# Environment-ArduinoNano33-V10_1-Top.net
KiCad netlist of a schematic drawn in EAGLE
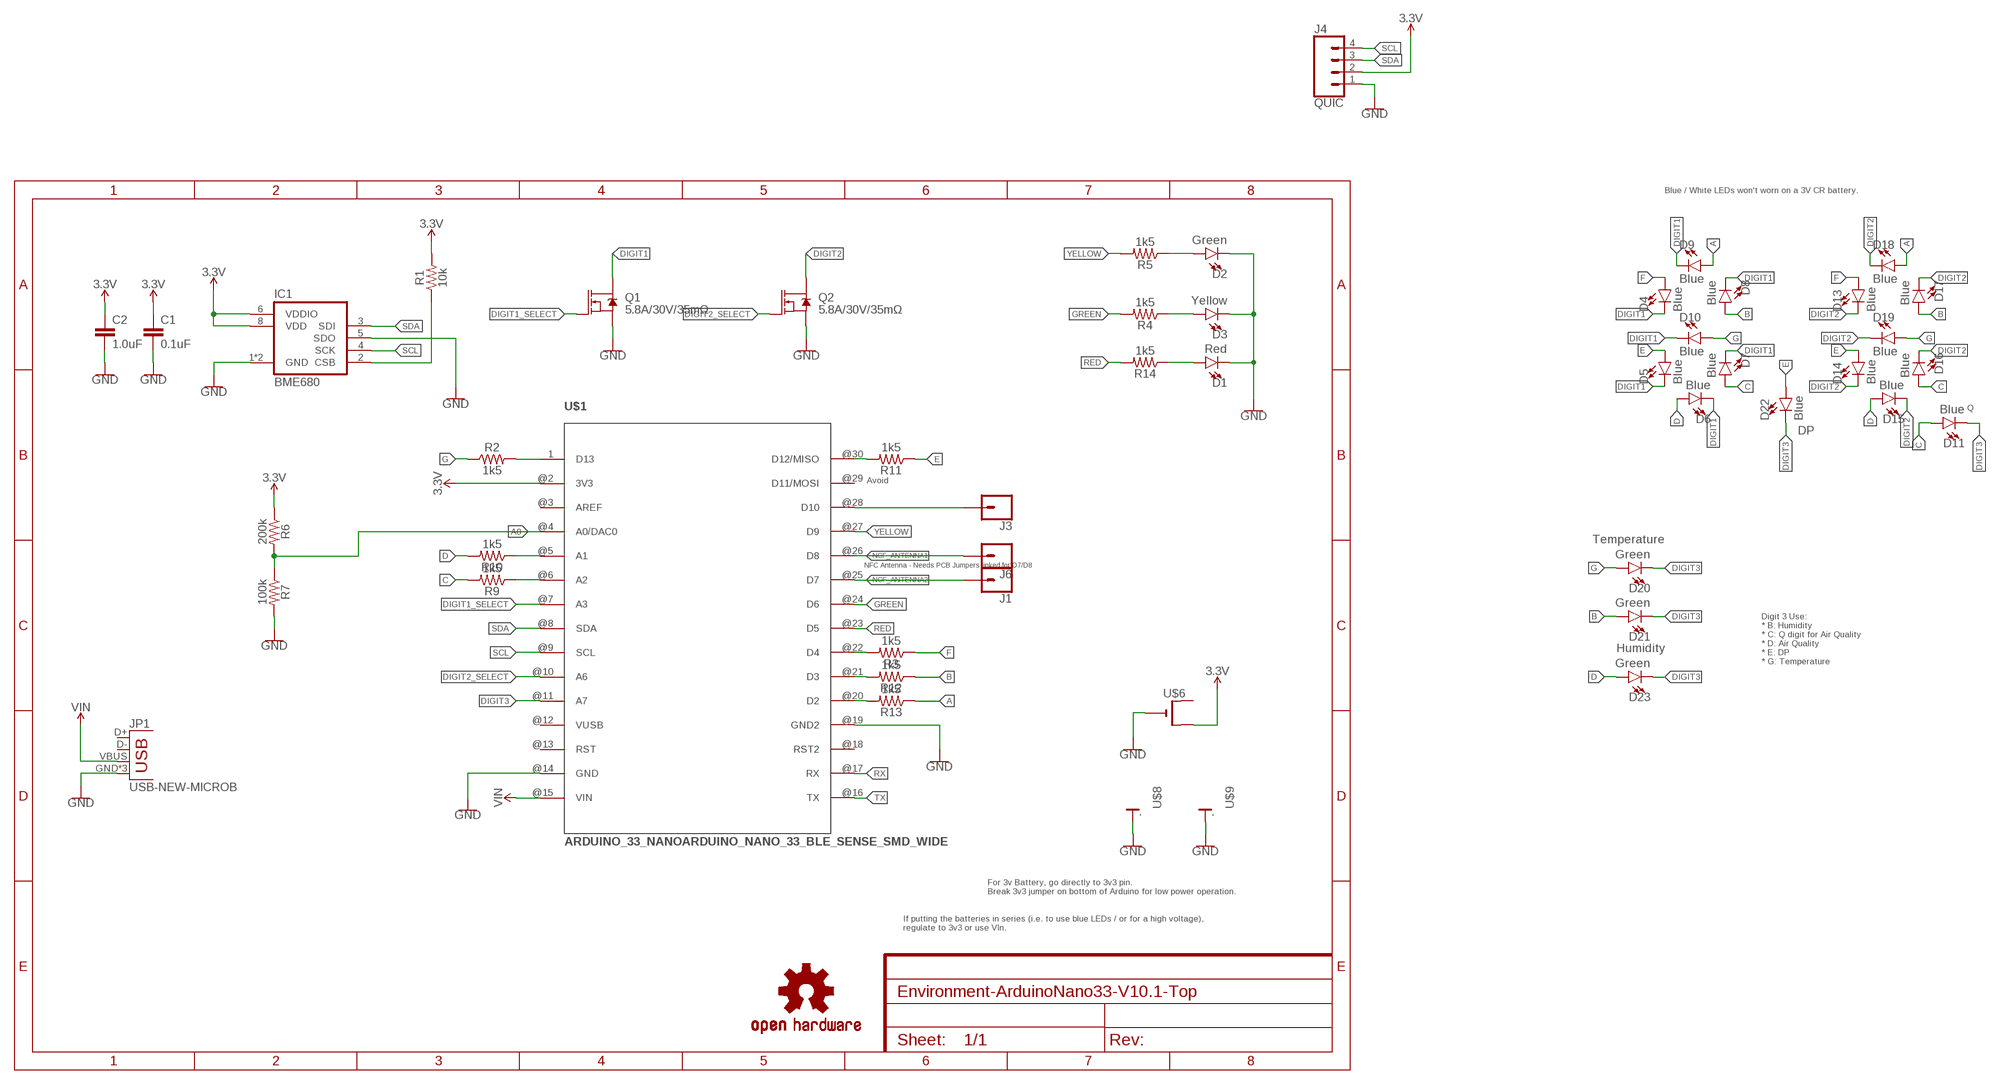
[diagram p0: schematic, sheet 1]

(export (version "E")
  (design (tool "Eeschema 10.0.6"))
  (components
    (comp (ref "C1")
      (value "0.1uF")
      (footprint "eagle-import:0805")
      (libsource (lib "eagle-import") (part "0.1UF-0805-25V"))
    )
    (comp (ref "C2")
      (value "1.0uF")
      (footprint "eagle-import:0805")
      (libsource (lib "eagle-import") (part "1.0UF-0805-25V-10%"))
    )
    (comp (ref "D1")
      (value "Red")
      (footprint "eagle-import:LED-1206")
      (libsource (lib "eagle-import") (part "LED1206"))
    )
    (comp (ref "D2")
      (value "Green")
      (footprint "eagle-import:LED-1206")
      (libsource (lib "eagle-import") (part "LED1206"))
    )
    (comp (ref "D3")
      (value "Yellow")
      (footprint "eagle-import:LED-1206")
      (libsource (lib "eagle-import") (part "LED1206"))
    )
    (comp (ref "D4")
      (value "Blue")
      (footprint "eagle-import:LED-1206")
      (libsource (lib "eagle-import") (part "LED1206"))
    )
    (comp (ref "D5")
      (value "Blue")
      (footprint "eagle-import:LED-1206")
      (libsource (lib "eagle-import") (part "LED1206"))
    )
    (comp (ref "D6")
      (value "Blue")
      (footprint "eagle-import:LED-1206")
      (libsource (lib "eagle-import") (part "LED1206"))
    )
    (comp (ref "D7")
      (value "Blue")
      (footprint "eagle-import:LED-1206")
      (libsource (lib "eagle-import") (part "LED1206"))
    )
    (comp (ref "D8")
      (value "Blue")
      (footprint "eagle-import:LED-1206")
      (libsource (lib "eagle-import") (part "LED1206"))
    )
    (comp (ref "D9")
      (value "Blue")
      (footprint "eagle-import:LED-1206")
      (libsource (lib "eagle-import") (part "LED1206"))
    )
    (comp (ref "D10")
      (value "Blue")
      (footprint "eagle-import:LED-1206")
      (libsource (lib "eagle-import") (part "LED1206"))
    )
    (comp (ref "D11")
      (value "Blue")
      (footprint "eagle-import:LED-1206")
      (libsource (lib "eagle-import") (part "LED1206"))
    )
    (comp (ref "D13")
      (value "Blue")
      (footprint "eagle-import:LED-1206")
      (libsource (lib "eagle-import") (part "LED1206"))
    )
    (comp (ref "D14")
      (value "Blue")
      (footprint "eagle-import:LED-1206")
      (libsource (lib "eagle-import") (part "LED1206"))
    )
    (comp (ref "D15")
      (value "Blue")
      (footprint "eagle-import:LED-1206")
      (libsource (lib "eagle-import") (part "LED1206"))
    )
    (comp (ref "D16")
      (value "Blue")
      (footprint "eagle-import:LED-1206")
      (libsource (lib "eagle-import") (part "LED1206"))
    )
    (comp (ref "D17")
      (value "Blue")
      (footprint "eagle-import:LED-1206")
      (libsource (lib "eagle-import") (part "LED1206"))
    )
    (comp (ref "D18")
      (value "Blue")
      (footprint "eagle-import:LED-1206")
      (libsource (lib "eagle-import") (part "LED1206"))
    )
    (comp (ref "D19")
      (value "Blue")
      (footprint "eagle-import:LED-1206")
      (libsource (lib "eagle-import") (part "LED1206"))
    )
    (comp (ref "D20")
      (value "Green")
      (footprint "eagle-import:LED-1206")
      (libsource (lib "eagle-import") (part "LED1206"))
    )
    (comp (ref "D21")
      (value "Green")
      (footprint "eagle-import:LED-1206")
      (libsource (lib "eagle-import") (part "LED1206"))
    )
    (comp (ref "D22")
      (value "Blue")
      (footprint "eagle-import:LED-1206")
      (libsource (lib "eagle-import") (part "LED1206"))
    )
    (comp (ref "D23")
      (value "Green")
      (footprint "eagle-import:LED-1206")
      (libsource (lib "eagle-import") (part "LED1206"))
    )
    (comp (ref "IC1")
      (value "BME680")
      (footprint "eagle-import:BME680")
      (libsource (lib "eagle-import") (part "BME680"))
    )
    (comp (ref "J1")
      (value "CONN_01")
      (footprint "eagle-import:1X01")
      (libsource (lib "eagle-import") (part "CONN_01"))
    )
    (comp (ref "J3")
      (value "CONN_01")
      (footprint "eagle-import:1X01")
      (libsource (lib "eagle-import") (part "CONN_01"))
    )
    (comp (ref "J4")
      (value "QUIC")
      (footprint "eagle-import:JST04_1MM_RA")
      (libsource (lib "eagle-import") (part "CONN_04SMD2"))
    )
    (comp (ref "J6")
      (value "CONN_01")
      (footprint "eagle-import:1X01")
      (libsource (lib "eagle-import") (part "CONN_01"))
    )
    (comp (ref "JP1")
      (value "USB-NEW-MICROB")
      (footprint "eagle-import:USB-MICROB")
      (libsource (lib "eagle-import") (part "USB-NEW-MICROB"))
    )
    (comp (ref "LOGO1")
      (value "OSHW-LOGOM")
      (footprint "eagle-import:OSHW-LOGO-M")
      (libsource (lib "eagle-import") (part "OSHW-LOGOM"))
    )
    (comp (ref "Q1")
      (value "5.8A/30V/35mΩ")
      (footprint "eagle-import:SOT23-3")
      (libsource (lib "eagle-import") (part "MOSFET-NCH-AO3404A"))
    )
    (comp (ref "Q2")
      (value "5.8A/30V/35mΩ")
      (footprint "eagle-import:SOT23-3")
      (libsource (lib "eagle-import") (part "MOSFET-NCH-AO3404A"))
    )
    (comp (ref "R1")
      (value "10k")
      (footprint "eagle-import:0805")
      (libsource (lib "eagle-import") (part "RESISTOR0805"))
    )
    (comp (ref "R2")
      (value "1k5")
      (footprint "eagle-import:0805")
      (libsource (lib "eagle-import") (part "RESISTOR0805"))
    )
    (comp (ref "R3")
      (value "1k5")
      (footprint "eagle-import:0805")
      (libsource (lib "eagle-import") (part "RESISTOR0805"))
    )
    (comp (ref "R4")
      (value "1k5")
      (footprint "eagle-import:0805")
      (libsource (lib "eagle-import") (part "RESISTOR0805"))
    )
    (comp (ref "R5")
      (value "1k5")
      (footprint "eagle-import:0805")
      (libsource (lib "eagle-import") (part "RESISTOR0805"))
    )
    (comp (ref "R6")
      (value "200k")
      (footprint "eagle-import:0805")
      (libsource (lib "eagle-import") (part "RESISTOR0805"))
    )
    (comp (ref "R7")
      (value "100k")
      (footprint "eagle-import:0805")
      (libsource (lib "eagle-import") (part "RESISTOR0805"))
    )
    (comp (ref "R9")
      (value "1k5")
      (footprint "eagle-import:0805")
      (libsource (lib "eagle-import") (part "RESISTOR0805"))
    )
    (comp (ref "R10")
      (value "1k5")
      (footprint "eagle-import:0805")
      (libsource (lib "eagle-import") (part "RESISTOR0805"))
    )
    (comp (ref "R11")
      (value "1k5")
      (footprint "eagle-import:0805")
      (libsource (lib "eagle-import") (part "RESISTOR0805"))
    )
    (comp (ref "R12")
      (value "1k5")
      (footprint "eagle-import:0805")
      (libsource (lib "eagle-import") (part "RESISTOR0805"))
    )
    (comp (ref "R13")
      (value "1k5")
      (footprint "eagle-import:0805")
      (libsource (lib "eagle-import") (part "RESISTOR0805"))
    )
    (comp (ref "R14")
      (value "1k5")
      (footprint "eagle-import:0805")
      (libsource (lib "eagle-import") (part "RESISTOR0805"))
    )
    (comp (ref "U$1")
      (value "ARDUINO_33_NANOARDUINO_NANO_33_BLE_SENSE_SMD_WIDE")
      (footprint "eagle-import:ARDUINO_NANO_33_SMD_WIDER_PADS")
      (libsource (lib "eagle-import") (part "ARDUINO_33_NANOARDUINO_NANO_33_BLE_SENSE_SMD_WIDE"))
    )
    (comp (ref "U$6")
      (value "CR2032SMT")
      (footprint "eagle-import:CR2032-SMD")
      (libsource (lib "eagle-import") (part "CR2032SMT"))
    )
    (comp (ref "U$8")
      (value "CR2032-SPLIT-PCBCR2032-NEGATIVE")
      (footprint "eagle-import:CR2032-SMD-NEGATIVE-TERMINAL")
      (libsource (lib "eagle-import") (part "CR2032-SPLIT-PCBCR2032-NEGATIVE"))
    )
    (comp (ref "U$9")
      (value "CR2032-SPLIT-PCBCR2032-NEGATIVE")
      (footprint "eagle-import:CR2032-SMD-NEGATIVE-TERMINAL")
      (libsource (lib "eagle-import") (part "CR2032-SPLIT-PCBCR2032-NEGATIVE"))
    )
  )
  (nets
    (net (code "1") (name "/VUSB") (class "Default")
      (node (ref "U$1") (pin "@12") (pinfunction "VUSB_@12") (pintype "power_in"))
    )
    (net (code "2") (name "3.3V") (class "Default")
      (node (ref "C1") (pin "1") (pinfunction "1_1") (pintype "passive"))
      (node (ref "C2") (pin "1") (pinfunction "1_1") (pintype "passive"))
      (node (ref "IC1") (pin "6") (pinfunction "VDDIO_6") (pintype "power_in"))
      (node (ref "IC1") (pin "8") (pinfunction "VDD_8") (pintype "power_in"))
      (node (ref "J4") (pin "2") (pinfunction "2_2") (pintype "passive"))
      (node (ref "R1") (pin "2") (pinfunction "2_2") (pintype "passive"))
      (node (ref "R6") (pin "1") (pinfunction "1_1") (pintype "passive"))
      (node (ref "U$1") (pin "@2") (pinfunction "3V3_@2") (pintype "power_in"))
      (node (ref "U$6") (pin "+$2") (pinfunction "+1_+$2") (pintype "passive"))
    )
    (net (code "3") (name "A") (class "Default")
      (node (ref "D18") (pin "A") (pinfunction "A_A") (pintype "passive"))
      (node (ref "D9") (pin "A") (pinfunction "A_A") (pintype "passive"))
      (node (ref "R13") (pin "1") (pinfunction "1_1") (pintype "passive"))
    )
    (net (code "4") (name "A0") (class "Default")
      (node (ref "R6") (pin "2") (pinfunction "2_2") (pintype "passive"))
      (node (ref "R7") (pin "1") (pinfunction "1_1") (pintype "passive"))
      (node (ref "U$1") (pin "@4") (pinfunction "A0/DAC0_@4") (pintype "bidirectional"))
    )
    (net (code "5") (name "B") (class "Default")
      (node (ref "D17") (pin "A") (pinfunction "A_A") (pintype "passive"))
      (node (ref "D21") (pin "A") (pinfunction "A_A") (pintype "passive"))
      (node (ref "D8") (pin "A") (pinfunction "A_A") (pintype "passive"))
      (node (ref "R12") (pin "1") (pinfunction "1_1") (pintype "passive"))
    )
    (net (code "6") (name "C") (class "Default")
      (node (ref "D11") (pin "A") (pinfunction "A_A") (pintype "passive"))
      (node (ref "D16") (pin "A") (pinfunction "A_A") (pintype "passive"))
      (node (ref "D7") (pin "A") (pinfunction "A_A") (pintype "passive"))
      (node (ref "R9") (pin "2") (pinfunction "2_2") (pintype "passive"))
    )
    (net (code "7") (name "D") (class "Default")
      (node (ref "D15") (pin "A") (pinfunction "A_A") (pintype "passive"))
      (node (ref "D23") (pin "A") (pinfunction "A_A") (pintype "passive"))
      (node (ref "D6") (pin "A") (pinfunction "A_A") (pintype "passive"))
      (node (ref "R10") (pin "2") (pinfunction "2_2") (pintype "passive"))
    )
    (net (code "8") (name "DIGIT1") (class "Default")
      (node (ref "D10") (pin "C") (pinfunction "C_C") (pintype "passive"))
      (node (ref "D4") (pin "C") (pinfunction "C_C") (pintype "passive"))
      (node (ref "D5") (pin "C") (pinfunction "C_C") (pintype "passive"))
      (node (ref "D6") (pin "C") (pinfunction "C_C") (pintype "passive"))
      (node (ref "D7") (pin "C") (pinfunction "C_C") (pintype "passive"))
      (node (ref "D8") (pin "C") (pinfunction "C_C") (pintype "passive"))
      (node (ref "D9") (pin "C") (pinfunction "C_C") (pintype "passive"))
      (node (ref "Q1") (pin "3") (pinfunction "D_3") (pintype "bidirectional"))
    )
    (net (code "9") (name "DIGIT1_SELECT") (class "Default")
      (node (ref "Q1") (pin "1") (pinfunction "G_1") (pintype "bidirectional"))
      (node (ref "U$1") (pin "@7") (pinfunction "A3_@7") (pintype "bidirectional"))
    )
    (net (code "10") (name "DIGIT2") (class "Default")
      (node (ref "D13") (pin "C") (pinfunction "C_C") (pintype "passive"))
      (node (ref "D14") (pin "C") (pinfunction "C_C") (pintype "passive"))
      (node (ref "D15") (pin "C") (pinfunction "C_C") (pintype "passive"))
      (node (ref "D16") (pin "C") (pinfunction "C_C") (pintype "passive"))
      (node (ref "D17") (pin "C") (pinfunction "C_C") (pintype "passive"))
      (node (ref "D18") (pin "C") (pinfunction "C_C") (pintype "passive"))
      (node (ref "D19") (pin "C") (pinfunction "C_C") (pintype "passive"))
      (node (ref "Q2") (pin "3") (pinfunction "D_3") (pintype "bidirectional"))
    )
    (net (code "11") (name "DIGIT2_SELECT") (class "Default")
      (node (ref "Q2") (pin "1") (pinfunction "G_1") (pintype "bidirectional"))
      (node (ref "U$1") (pin "@10") (pinfunction "A6_@10") (pintype "bidirectional"))
    )
    (net (code "12") (name "DIGIT3") (class "Default")
      (node (ref "D11") (pin "C") (pinfunction "C_C") (pintype "passive"))
      (node (ref "D20") (pin "C") (pinfunction "C_C") (pintype "passive"))
      (node (ref "D21") (pin "C") (pinfunction "C_C") (pintype "passive"))
      (node (ref "D22") (pin "C") (pinfunction "C_C") (pintype "passive"))
      (node (ref "D23") (pin "C") (pinfunction "C_C") (pintype "passive"))
      (node (ref "U$1") (pin "@11") (pinfunction "A7_@11") (pintype "bidirectional"))
    )
    (net (code "13") (name "E") (class "Default")
      (node (ref "D14") (pin "A") (pinfunction "A_A") (pintype "passive"))
      (node (ref "D22") (pin "A") (pinfunction "A_A") (pintype "passive"))
      (node (ref "D5") (pin "A") (pinfunction "A_A") (pintype "passive"))
      (node (ref "R11") (pin "1") (pinfunction "1_1") (pintype "passive"))
    )
    (net (code "14") (name "F") (class "Default")
      (node (ref "D13") (pin "A") (pinfunction "A_A") (pintype "passive"))
      (node (ref "D4") (pin "A") (pinfunction "A_A") (pintype "passive"))
      (node (ref "R3") (pin "1") (pinfunction "1_1") (pintype "passive"))
    )
    (net (code "15") (name "G") (class "Default")
      (node (ref "D10") (pin "A") (pinfunction "A_A") (pintype "passive"))
      (node (ref "D19") (pin "A") (pinfunction "A_A") (pintype "passive"))
      (node (ref "D20") (pin "A") (pinfunction "A_A") (pintype "passive"))
      (node (ref "R2") (pin "1") (pinfunction "1_1") (pintype "passive"))
    )
    (net (code "16") (name "GND") (class "Default")
      (node (ref "C1") (pin "2") (pinfunction "2_2") (pintype "passive"))
      (node (ref "C2") (pin "2") (pinfunction "2_2") (pintype "passive"))
      (node (ref "D1") (pin "C") (pinfunction "C_C") (pintype "passive"))
      (node (ref "D2") (pin "C") (pinfunction "C_C") (pintype "passive"))
      (node (ref "D3") (pin "C") (pinfunction "C_C") (pintype "passive"))
      (node (ref "IC1") (pin "1") (pinfunction "GND_1") (pintype "power_in"))
      (node (ref "IC1") (pin "5") (pinfunction "SDO_5") (pintype "output"))
      (node (ref "IC1") (pin "7") (pinfunction "GND_7") (pintype "power_in"))
      (node (ref "J4") (pin "1") (pinfunction "1_1") (pintype "passive"))
      (node (ref "JP1") (pin "GND") (pinfunction "GND_GND") (pintype "bidirectional"))
      (node (ref "JP1") (pin "MT1") (pinfunction "GND_MT1") (pintype "bidirectional"))
      (node (ref "JP1") (pin "MT2") (pinfunction "GND_MT2") (pintype "bidirectional"))
      (node (ref "Q1") (pin "2") (pinfunction "S_2") (pintype "bidirectional"))
      (node (ref "Q2") (pin "2") (pinfunction "S_2") (pintype "bidirectional"))
      (node (ref "R7") (pin "2") (pinfunction "2_2") (pintype "passive"))
      (node (ref "U$1") (pin "@14") (pinfunction "GND_@14") (pintype "bidirectional"))
      (node (ref "U$1") (pin "@19") (pinfunction "GND2_@19") (pintype "bidirectional"))
      (node (ref "U$6") (pin "-") (pinfunction "-_-") (pintype "passive"))
      (node (ref "U$8") (pin "-") (pinfunction "-_-") (pintype "power_in"))
      (node (ref "U$9") (pin "-") (pinfunction "-_-") (pintype "power_in"))
    )
    (net (code "17") (name "GREEN") (class "Default")
      (node (ref "R4") (pin "2") (pinfunction "2_2") (pintype "passive"))
      (node (ref "U$1") (pin "@24") (pinfunction "D6_@24") (pintype "bidirectional"))
    )
    (net (code "18") (name "NCF_ANTENNA1") (class "Default")
      (node (ref "J6") (pin "1") (pinfunction "1_1") (pintype "passive"))
      (node (ref "U$1") (pin "@26") (pinfunction "D8_@26") (pintype "bidirectional"))
    )
    (net (code "19") (name "NCF_ANTENNA2") (class "Default")
      (node (ref "J1") (pin "1") (pinfunction "1_1") (pintype "passive"))
      (node (ref "U$1") (pin "@25") (pinfunction "D7_@25") (pintype "bidirectional"))
    )
    (net (code "20") (name "Net-(D1-PadA)") (class "Default")
      (node (ref "D1") (pin "A") (pinfunction "A_A") (pintype "passive"))
      (node (ref "R14") (pin "1") (pinfunction "1_1") (pintype "passive"))
    )
    (net (code "21") (name "Net-(D2-PadA)") (class "Default")
      (node (ref "D2") (pin "A") (pinfunction "A_A") (pintype "passive"))
      (node (ref "R5") (pin "1") (pinfunction "1_1") (pintype "passive"))
    )
    (net (code "22") (name "Net-(D3-PadA)") (class "Default")
      (node (ref "D3") (pin "A") (pinfunction "A_A") (pintype "passive"))
      (node (ref "R4") (pin "1") (pinfunction "1_1") (pintype "passive"))
    )
    (net (code "23") (name "Net-(IC1-CSB)") (class "Default")
      (node (ref "IC1") (pin "2") (pinfunction "CSB_2") (pintype "input"))
      (node (ref "R1") (pin "1") (pinfunction "1_1") (pintype "passive"))
    )
    (net (code "24") (name "Net-(U$1-A1)") (class "Default")
      (node (ref "R10") (pin "1") (pinfunction "1_1") (pintype "passive"))
      (node (ref "U$1") (pin "@5") (pinfunction "A1_@5") (pintype "bidirectional"))
    )
    (net (code "25") (name "Net-(U$1-A2)") (class "Default")
      (node (ref "R9") (pin "1") (pinfunction "1_1") (pintype "passive"))
      (node (ref "U$1") (pin "@6") (pinfunction "A2_@6") (pintype "bidirectional"))
    )
    (net (code "26") (name "Net-(U$1-D2)") (class "Default")
      (node (ref "R13") (pin "2") (pinfunction "2_2") (pintype "passive"))
      (node (ref "U$1") (pin "@20") (pinfunction "D2_@20") (pintype "bidirectional"))
    )
    (net (code "27") (name "Net-(U$1-D3)") (class "Default")
      (node (ref "R12") (pin "2") (pinfunction "2_2") (pintype "passive"))
      (node (ref "U$1") (pin "@21") (pinfunction "D3_@21") (pintype "bidirectional"))
    )
    (net (code "28") (name "Net-(U$1-D4)") (class "Default")
      (node (ref "R3") (pin "2") (pinfunction "2_2") (pintype "passive"))
      (node (ref "U$1") (pin "@22") (pinfunction "D4_@22") (pintype "bidirectional"))
    )
    (net (code "29") (name "Net-(U$1-D10)") (class "Default")
      (node (ref "J3") (pin "1") (pinfunction "1_1") (pintype "passive"))
      (node (ref "U$1") (pin "@28") (pinfunction "D10_@28") (pintype "bidirectional"))
    )
    (net (code "30") (name "Net-(U$1-D12{slash}MISO)") (class "Default")
      (node (ref "R11") (pin "2") (pinfunction "2_2") (pintype "passive"))
      (node (ref "U$1") (pin "@30") (pinfunction "D12/MISO_@30") (pintype "bidirectional"))
    )
    (net (code "31") (name "Net-(U$1-D13)") (class "Default")
      (node (ref "R2") (pin "2") (pinfunction "2_2") (pintype "passive"))
      (node (ref "U$1") (pin "1") (pinfunction "D13_1") (pintype "bidirectional"))
    )
    (net (code "32") (name "RED") (class "Default")
      (node (ref "R14") (pin "2") (pinfunction "2_2") (pintype "passive"))
      (node (ref "U$1") (pin "@23") (pinfunction "D5_@23") (pintype "bidirectional"))
    )
    (net (code "33") (name "RX") (class "Default")
      (node (ref "U$1") (pin "@17") (pinfunction "RX_@17") (pintype "bidirectional"))
    )
    (net (code "34") (name "SCL") (class "Default")
      (node (ref "IC1") (pin "4") (pinfunction "SCK_4") (pintype "input"))
      (node (ref "J4") (pin "4") (pinfunction "4_4") (pintype "passive"))
      (node (ref "U$1") (pin "@9") (pinfunction "SCL_@9") (pintype "bidirectional"))
    )
    (net (code "35") (name "SDA") (class "Default")
      (node (ref "IC1") (pin "3") (pinfunction "SDI_3") (pintype "input"))
      (node (ref "J4") (pin "3") (pinfunction "3_3") (pintype "passive"))
      (node (ref "U$1") (pin "@8") (pinfunction "SDA_@8") (pintype "bidirectional"))
    )
    (net (code "36") (name "TX") (class "Default")
      (node (ref "U$1") (pin "@16") (pinfunction "TX_@16") (pintype "bidirectional"))
    )
    (net (code "37") (name "VIN") (class "Default")
      (node (ref "JP1") (pin "VBUS") (pinfunction "VBUS_VBUS") (pintype "bidirectional"))
      (node (ref "U$1") (pin "@15") (pinfunction "VIN_@15") (pintype "power_in"))
    )
    (net (code "38") (name "YELLOW") (class "Default")
      (node (ref "R5") (pin "2") (pinfunction "2_2") (pintype "passive"))
      (node (ref "U$1") (pin "@27") (pinfunction "D9_@27") (pintype "bidirectional"))
    )
    (net (code "39") (name "unconnected-(JP1-PadD+)") (class "Default")
      (node (ref "JP1") (pin "D+") (pinfunction "D+_D+") (pintype "bidirectional"))
    )
    (net (code "40") (name "unconnected-(JP1-PadD-)") (class "Default")
      (node (ref "JP1") (pin "D-") (pinfunction "D-_D-") (pintype "bidirectional"))
    )
    (net (code "41") (name "unconnected-(U$1-AREF-Pad@3)") (class "Default")
      (node (ref "U$1") (pin "@3") (pinfunction "AREF_@3") (pintype "output"))
    )
    (net (code "42") (name "unconnected-(U$1-D11{slash}MOSI-Pad@29)") (class "Default")
      (node (ref "U$1") (pin "@29") (pinfunction "D11/MOSI_@29") (pintype "bidirectional"))
    )
    (net (code "43") (name "unconnected-(U$1-RST-Pad@13)") (class "Default")
      (node (ref "U$1") (pin "@13") (pinfunction "RST_@13") (pintype "bidirectional"))
    )
    (net (code "44") (name "unconnected-(U$1-RST2-Pad@18)") (class "Default")
      (node (ref "U$1") (pin "@18") (pinfunction "RST2_@18") (pintype "bidirectional"))
    )
    (net (code "45") (name "unconnected-(U$6-+-Pad+$1)") (class "Default")
      (node (ref "U$6") (pin "+$1") (pinfunction "+_+$1") (pintype "passive"))
    )
  )
)
